# STM32F767VG.net
KiCad netlist of a schematic drawn in EAGLE
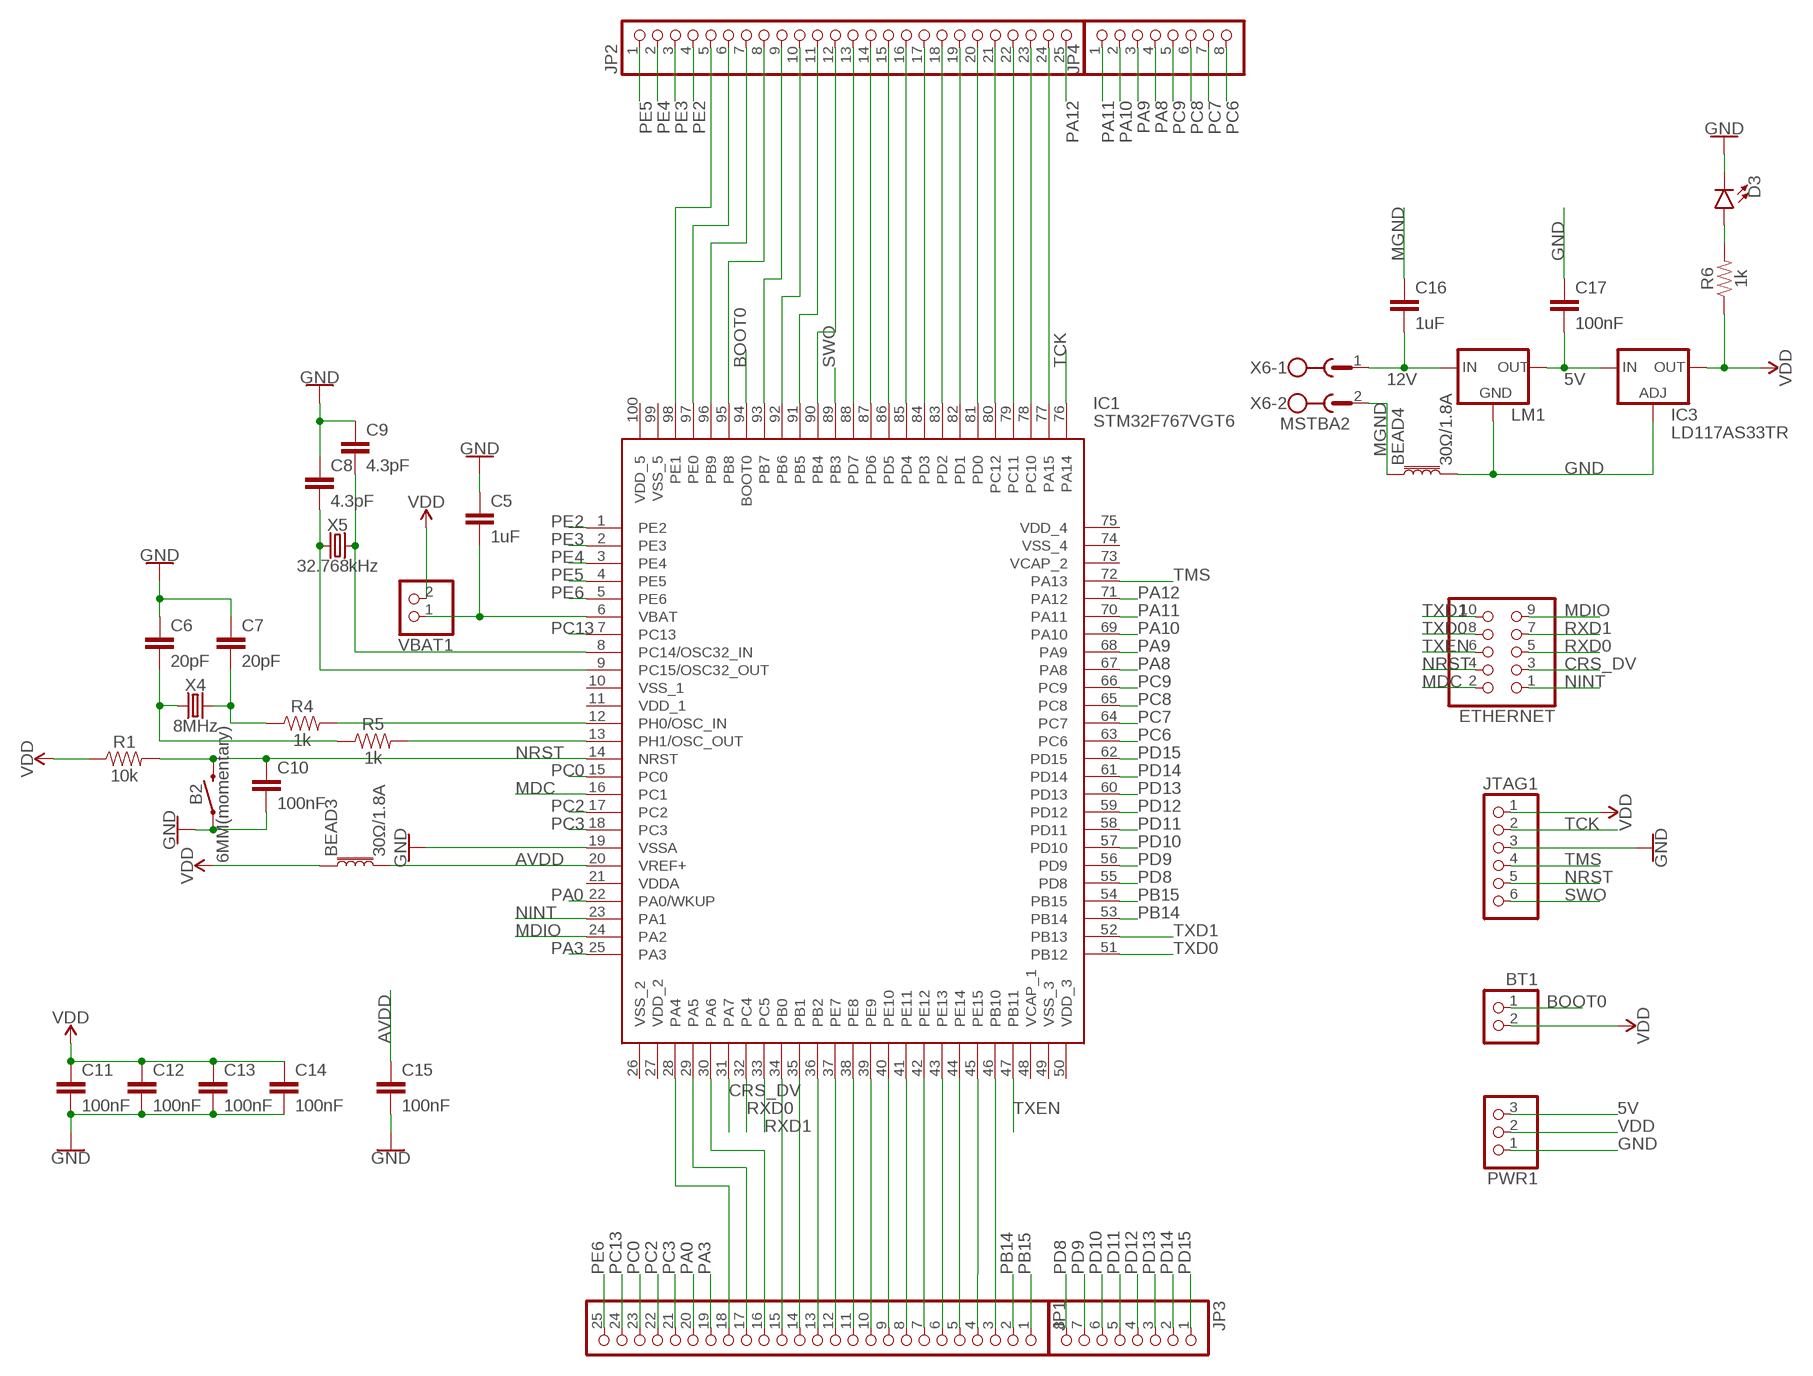
[diagram p0: schematic, sheet 1]

(export (version "E")
  (design (tool "Eeschema 10.0.6"))
  (components
    (comp (ref "B2")
      (value "6MM(momentary)")
      (footprint "eagle-import:TACTILE_SWITCH_PTH_6.0MM")
      (libsource (lib "eagle-import") (part "MOMENTARY-SWITCH-SPST-PTH-6.0MM"))
    )
    (comp (ref "BEAD3")
      (value "30Ω/1.8A")
      (footprint "eagle-import:0603")
      (libsource (lib "eagle-import") (part "FERRITE_BEAD-0603"))
    )
    (comp (ref "BEAD4")
      (value "30Ω/1.8A")
      (footprint "eagle-import:0603")
      (libsource (lib "eagle-import") (part "FERRITE_BEAD-0603"))
    )
    (comp (ref "BT1")
      (value "PINHD-1X2")
      (footprint "eagle-import:1X02")
      (libsource (lib "eagle-import") (part "PINHD-1X2"))
    )
    (comp (ref "C5")
      (value "1uF")
      (footprint "eagle-import:C050-030-075")
      (libsource (lib "eagle-import") (part "C5P"))
    )
    (comp (ref "C6")
      (value "20pF")
      (footprint "eagle-import:C025-030X050")
      (libsource (lib "eagle-import") (part "C2.5P"))
    )
    (comp (ref "C7")
      (value "20pF")
      (footprint "eagle-import:C025-030X050")
      (libsource (lib "eagle-import") (part "C2.5P"))
    )
    (comp (ref "C8")
      (value "4.3pF")
      (footprint "eagle-import:C025-030X050")
      (libsource (lib "eagle-import") (part "C2.5P"))
    )
    (comp (ref "C9")
      (value "4.3pF")
      (footprint "eagle-import:C025-030X050")
      (libsource (lib "eagle-import") (part "C2.5P"))
    )
    (comp (ref "C10")
      (value "100nF")
      (footprint "eagle-import:C025-030X050")
      (libsource (lib "eagle-import") (part "C2.5P"))
    )
    (comp (ref "C11")
      (value "100nF")
      (footprint "eagle-import:C025-030X050")
      (libsource (lib "eagle-import") (part "C2.5P"))
    )
    (comp (ref "C12")
      (value "100nF")
      (footprint "eagle-import:C025-030X050")
      (libsource (lib "eagle-import") (part "C2.5P"))
    )
    (comp (ref "C13")
      (value "100nF")
      (footprint "eagle-import:C025-030X050")
      (libsource (lib "eagle-import") (part "C2.5P"))
    )
    (comp (ref "C14")
      (value "100nF")
      (footprint "eagle-import:C025-030X050")
      (libsource (lib "eagle-import") (part "C2.5P"))
    )
    (comp (ref "C15")
      (value "100nF")
      (footprint "eagle-import:C025-030X050")
      (libsource (lib "eagle-import") (part "C2.5P"))
    )
    (comp (ref "C16")
      (value "1uF")
      (footprint "eagle-import:C050-030-075")
      (libsource (lib "eagle-import") (part "C5P"))
    )
    (comp (ref "C17")
      (value "100nF")
      (footprint "eagle-import:C025-030X050")
      (libsource (lib "eagle-import") (part "C2.5P"))
    )
    (comp (ref "D3")
      (value "LED5MM")
      (footprint "eagle-import:LED_5MM")
      (libsource (lib "eagle-import") (part "LED5MM"))
    )
    (comp (ref "ETHERNET")
      (value "PINHD-2X5")
      (footprint "eagle-import:2X05")
      (libsource (lib "eagle-import") (part "PINHD-2X5"))
    )
    (comp (ref "IC1")
      (value "STM32F767VGT6")
      (footprint "eagle-import:QFP50P1600X1600X160-100N")
      (libsource (lib "eagle-import") (part "STM32F767VGT6"))
    )
    (comp (ref "IC3")
      (value "LD117AS33TR")
      (footprint "eagle-import:SOT223")
      (libsource (lib "eagle-import") (part "LD117A?S33TR"))
    )
    (comp (ref "JP1")
      (value "PINHD-1X25")
      (footprint "eagle-import:1X25")
      (libsource (lib "eagle-import") (part "PINHD-1X25"))
    )
    (comp (ref "JP2")
      (value "PINHD-1X25")
      (footprint "eagle-import:1X25")
      (libsource (lib "eagle-import") (part "PINHD-1X25"))
    )
    (comp (ref "JP3")
      (value "PINHD-1X8")
      (footprint "eagle-import:1X08")
      (libsource (lib "eagle-import") (part "PINHD-1X8"))
    )
    (comp (ref "JP4")
      (value "PINHD-1X8")
      (footprint "eagle-import:1X08")
      (libsource (lib "eagle-import") (part "PINHD-1X8"))
    )
    (comp (ref "JTAG1")
      (value "PINHD-1X6")
      (footprint "eagle-import:1X06")
      (libsource (lib "eagle-import") (part "PINHD-1X6"))
    )
    (comp (ref "LM1")
      (value "V_REG_78XX-TO-220")
      (footprint "eagle-import:TO-220-ALT")
      (libsource (lib "eagle-import") (part "V_REG_78XX-TO-220"))
    )
    (comp (ref "PWR1")
      (value "PINHD-1X3")
      (footprint "eagle-import:1X03")
      (libsource (lib "eagle-import") (part "PINHD-1X3"))
    )
    (comp (ref "R1")
      (value "10k")
      (footprint "eagle-import:AXIAL-0.3")
      (libsource (lib "eagle-import") (part "10KOHM-HORIZ-1/4W-1%"))
    )
    (comp (ref "R4")
      (value "1k")
      (footprint "eagle-import:AXIAL-0.3")
      (libsource (lib "eagle-import") (part "10KOHM-HORIZ-1/4W-1%"))
    )
    (comp (ref "R5")
      (value "1k")
      (footprint "eagle-import:AXIAL-0.3")
      (libsource (lib "eagle-import") (part "10KOHM-HORIZ-1/4W-1%"))
    )
    (comp (ref "R6")
      (value "1k")
      (footprint "eagle-import:AXIAL-0.3")
      (libsource (lib "eagle-import") (part "1KOHM-HORIZ-1/4W-1%"))
    )
    (comp (ref "VBAT1")
      (value "PINHD-1X2")
      (footprint "eagle-import:1X02")
      (libsource (lib "eagle-import") (part "PINHD-1X2"))
    )
    (comp (ref "X4")
      (value "8MHz")
      (footprint "eagle-import:HC49UP")
      (libsource (lib "eagle-import") (part "CRYSTAL-8MHZSMD-HC49UP"))
    )
    (comp (ref "X5")
      (value "32.768kHz")
      (footprint "eagle-import:CRYSTAL-PTH-2X6-CYL")
      (libsource (lib "eagle-import") (part "CRYSTAL-32.768KHZPTH-2X6"))
    )
    (comp (ref "X6")
      (value "MSTBA2")
      (footprint "eagle-import:MSTBA2")
      (fields (field (name "MF") "FARNELL") (field (name "MPN") "1757242"))
      (libsource (lib "eagle-import") (part "MSTBA2"))
    )
  )
  (nets
    (net (code "1") (name "/5V") (class "Default")
      (node (ref "C17") (pin "2") (pinfunction "2_2") (pintype "passive"))
      (node (ref "IC3") (pin "3") (pinfunction "IN_3") (pintype "input"))
      (node (ref "LM1") (pin "OUT") (pinfunction "OUT_OUT") (pintype "passive"))
      (node (ref "PWR1") (pin "3") (pinfunction "3_3") (pintype "passive"))
    )
    (net (code "2") (name "/12V") (class "Default")
      (node (ref "C16") (pin "2") (pinfunction "2_2") (pintype "passive"))
      (node (ref "LM1") (pin "IN") (pinfunction "IN_IN") (pintype "input"))
      (node (ref "X6") (pin "1") (pinfunction "1_1") (pintype "passive"))
    )
    (net (code "3") (name "/AVDD") (class "Default")
      (node (ref "BEAD3") (pin "2") (pinfunction "2_2") (pintype "passive"))
      (node (ref "C15") (pin "1") (pinfunction "1_1") (pintype "passive"))
      (node (ref "IC1") (pin "20") (pinfunction "VREF+_20") (pintype "power_in"))
    )
    (net (code "4") (name "/BOOT0") (class "Default")
      (node (ref "BT1") (pin "1") (pinfunction "1_1") (pintype "passive"))
      (node (ref "IC1") (pin "94") (pinfunction "BOOT0_94") (pintype "bidirectional"))
    )
    (net (code "5") (name "/CRS_DV") (class "Default")
      (node (ref "ETHERNET") (pin "3") (pinfunction "3_3") (pintype "passive"))
      (node (ref "IC1") (pin "31") (pinfunction "PA7_31") (pintype "bidirectional"))
    )
    (net (code "6") (name "/MDC") (class "Default")
      (node (ref "ETHERNET") (pin "2") (pinfunction "2_2") (pintype "passive"))
      (node (ref "IC1") (pin "16") (pinfunction "PC1_16") (pintype "bidirectional"))
    )
    (net (code "7") (name "/MDIO") (class "Default")
      (node (ref "ETHERNET") (pin "9") (pinfunction "9_9") (pintype "passive"))
      (node (ref "IC1") (pin "24") (pinfunction "PA2_24") (pintype "bidirectional"))
    )
    (net (code "8") (name "/MGND") (class "Default")
      (node (ref "BEAD4") (pin "1") (pinfunction "1_1") (pintype "passive"))
      (node (ref "C16") (pin "1") (pinfunction "1_1") (pintype "passive"))
      (node (ref "X6") (pin "2") (pinfunction "1_2") (pintype "passive"))
    )
    (net (code "9") (name "/NINT") (class "Default")
      (node (ref "ETHERNET") (pin "1") (pinfunction "1_1") (pintype "passive"))
      (node (ref "IC1") (pin "23") (pinfunction "PA1_23") (pintype "bidirectional"))
    )
    (net (code "10") (name "/NRST") (class "Default")
      (node (ref "B2") (pin "3") (pinfunction "2_3") (pintype "passive"))
      (node (ref "C10") (pin "1") (pinfunction "1_1") (pintype "passive"))
      (node (ref "ETHERNET") (pin "4") (pinfunction "4_4") (pintype "passive"))
      (node (ref "IC1") (pin "14") (pinfunction "NRST_14") (pintype "bidirectional"))
      (node (ref "JTAG1") (pin "5") (pinfunction "5_5") (pintype "passive"))
      (node (ref "R1") (pin "P$2") (pinfunction "2_P$2") (pintype "passive"))
    )
    (net (code "11") (name "/PA0") (class "Default")
      (node (ref "IC1") (pin "22") (pinfunction "PA0/WKUP_22") (pintype "bidirectional"))
      (node (ref "JP1") (pin "20") (pinfunction "20_20") (pintype "passive"))
    )
    (net (code "12") (name "/PA3") (class "Default")
      (node (ref "IC1") (pin "25") (pinfunction "PA3_25") (pintype "bidirectional"))
      (node (ref "JP1") (pin "19") (pinfunction "19_19") (pintype "passive"))
    )
    (net (code "13") (name "/PA8") (class "Default")
      (node (ref "IC1") (pin "67") (pinfunction "PA8_67") (pintype "bidirectional"))
      (node (ref "JP4") (pin "4") (pinfunction "4_4") (pintype "passive"))
    )
    (net (code "14") (name "/PA9") (class "Default")
      (node (ref "IC1") (pin "68") (pinfunction "PA9_68") (pintype "bidirectional"))
      (node (ref "JP4") (pin "3") (pinfunction "3_3") (pintype "passive"))
    )
    (net (code "15") (name "/PA10") (class "Default")
      (node (ref "IC1") (pin "69") (pinfunction "PA10_69") (pintype "bidirectional"))
      (node (ref "JP4") (pin "2") (pinfunction "2_2") (pintype "passive"))
    )
    (net (code "16") (name "/PA11") (class "Default")
      (node (ref "IC1") (pin "70") (pinfunction "PA11_70") (pintype "bidirectional"))
      (node (ref "JP4") (pin "1") (pinfunction "1_1") (pintype "passive"))
    )
    (net (code "17") (name "/PA12") (class "Default")
      (node (ref "IC1") (pin "71") (pinfunction "PA12_71") (pintype "bidirectional"))
      (node (ref "JP2") (pin "25") (pinfunction "25_25") (pintype "passive"))
    )
    (net (code "18") (name "/PB14") (class "Default")
      (node (ref "IC1") (pin "53") (pinfunction "PB14_53") (pintype "bidirectional"))
      (node (ref "JP1") (pin "2") (pinfunction "2_2") (pintype "passive"))
    )
    (net (code "19") (name "/PB15") (class "Default")
      (node (ref "IC1") (pin "54") (pinfunction "PB15_54") (pintype "bidirectional"))
      (node (ref "JP1") (pin "1") (pinfunction "1_1") (pintype "passive"))
    )
    (net (code "20") (name "/PC0") (class "Default")
      (node (ref "IC1") (pin "15") (pinfunction "PC0_15") (pintype "bidirectional"))
      (node (ref "JP1") (pin "23") (pinfunction "23_23") (pintype "passive"))
    )
    (net (code "21") (name "/PC2") (class "Default")
      (node (ref "IC1") (pin "17") (pinfunction "PC2_17") (pintype "bidirectional"))
      (node (ref "JP1") (pin "22") (pinfunction "22_22") (pintype "passive"))
    )
    (net (code "22") (name "/PC3") (class "Default")
      (node (ref "IC1") (pin "18") (pinfunction "PC3_18") (pintype "bidirectional"))
      (node (ref "JP1") (pin "21") (pinfunction "21_21") (pintype "passive"))
    )
    (net (code "23") (name "/PC6") (class "Default")
      (node (ref "IC1") (pin "63") (pinfunction "PC6_63") (pintype "bidirectional"))
      (node (ref "JP4") (pin "8") (pinfunction "8_8") (pintype "passive"))
    )
    (net (code "24") (name "/PC7") (class "Default")
      (node (ref "IC1") (pin "64") (pinfunction "PC7_64") (pintype "bidirectional"))
      (node (ref "JP4") (pin "7") (pinfunction "7_7") (pintype "passive"))
    )
    (net (code "25") (name "/PC8") (class "Default")
      (node (ref "IC1") (pin "65") (pinfunction "PC8_65") (pintype "bidirectional"))
      (node (ref "JP4") (pin "6") (pinfunction "6_6") (pintype "passive"))
    )
    (net (code "26") (name "/PC9") (class "Default")
      (node (ref "IC1") (pin "66") (pinfunction "PC9_66") (pintype "bidirectional"))
      (node (ref "JP4") (pin "5") (pinfunction "5_5") (pintype "passive"))
    )
    (net (code "27") (name "/PC13") (class "Default")
      (node (ref "IC1") (pin "7") (pinfunction "PC13_7") (pintype "bidirectional"))
      (node (ref "JP1") (pin "24") (pinfunction "24_24") (pintype "passive"))
    )
    (net (code "28") (name "/PD8") (class "Default")
      (node (ref "IC1") (pin "55") (pinfunction "PD8_55") (pintype "bidirectional"))
      (node (ref "JP3") (pin "8") (pinfunction "8_8") (pintype "passive"))
    )
    (net (code "29") (name "/PD9") (class "Default")
      (node (ref "IC1") (pin "56") (pinfunction "PD9_56") (pintype "bidirectional"))
      (node (ref "JP3") (pin "7") (pinfunction "7_7") (pintype "passive"))
    )
    (net (code "30") (name "/PD10") (class "Default")
      (node (ref "IC1") (pin "57") (pinfunction "PD10_57") (pintype "bidirectional"))
      (node (ref "JP3") (pin "6") (pinfunction "6_6") (pintype "passive"))
    )
    (net (code "31") (name "/PD11") (class "Default")
      (node (ref "IC1") (pin "58") (pinfunction "PD11_58") (pintype "bidirectional"))
      (node (ref "JP3") (pin "5") (pinfunction "5_5") (pintype "passive"))
    )
    (net (code "32") (name "/PD12") (class "Default")
      (node (ref "IC1") (pin "59") (pinfunction "PD12_59") (pintype "bidirectional"))
      (node (ref "JP3") (pin "4") (pinfunction "4_4") (pintype "passive"))
    )
    (net (code "33") (name "/PD13") (class "Default")
      (node (ref "IC1") (pin "60") (pinfunction "PD13_60") (pintype "bidirectional"))
      (node (ref "JP3") (pin "3") (pinfunction "3_3") (pintype "passive"))
    )
    (net (code "34") (name "/PD14") (class "Default")
      (node (ref "IC1") (pin "61") (pinfunction "PD14_61") (pintype "bidirectional"))
      (node (ref "JP3") (pin "2") (pinfunction "2_2") (pintype "passive"))
    )
    (net (code "35") (name "/PD15") (class "Default")
      (node (ref "IC1") (pin "62") (pinfunction "PD15_62") (pintype "bidirectional"))
      (node (ref "JP3") (pin "1") (pinfunction "1_1") (pintype "passive"))
    )
    (net (code "36") (name "/PE2") (class "Default")
      (node (ref "IC1") (pin "1") (pinfunction "PE2_1") (pintype "bidirectional"))
      (node (ref "IC1") (pin "98") (pinfunction "PE1_98") (pintype "bidirectional"))
      (node (ref "JP2") (pin "4") (pinfunction "4_4") (pintype "passive"))
      (node (ref "JP2") (pin "5") (pinfunction "5_5") (pintype "passive"))
    )
    (net (code "37") (name "/PE3") (class "Default")
      (node (ref "IC1") (pin "2") (pinfunction "PE3_2") (pintype "bidirectional"))
      (node (ref "JP2") (pin "3") (pinfunction "3_3") (pintype "passive"))
    )
    (net (code "38") (name "/PE4") (class "Default")
      (node (ref "IC1") (pin "3") (pinfunction "PE4_3") (pintype "bidirectional"))
      (node (ref "JP2") (pin "2") (pinfunction "2_2") (pintype "passive"))
    )
    (net (code "39") (name "/PE5") (class "Default")
      (node (ref "IC1") (pin "4") (pinfunction "PE5_4") (pintype "bidirectional"))
      (node (ref "JP2") (pin "1") (pinfunction "1_1") (pintype "passive"))
    )
    (net (code "40") (name "/PE6") (class "Default")
      (node (ref "IC1") (pin "5") (pinfunction "PE6_5") (pintype "bidirectional"))
      (node (ref "JP1") (pin "25") (pinfunction "25_25") (pintype "passive"))
    )
    (net (code "41") (name "/RXD0") (class "Default")
      (node (ref "ETHERNET") (pin "5") (pinfunction "5_5") (pintype "passive"))
      (node (ref "IC1") (pin "32") (pinfunction "PC4_32") (pintype "bidirectional"))
    )
    (net (code "42") (name "/RXD1") (class "Default")
      (node (ref "ETHERNET") (pin "7") (pinfunction "7_7") (pintype "passive"))
      (node (ref "IC1") (pin "33") (pinfunction "PC5_33") (pintype "bidirectional"))
    )
    (net (code "43") (name "/SWO") (class "Default")
      (node (ref "IC1") (pin "89") (pinfunction "PB3_89") (pintype "bidirectional"))
      (node (ref "JTAG1") (pin "6") (pinfunction "6_6") (pintype "passive"))
    )
    (net (code "44") (name "/TCK") (class "Default")
      (node (ref "IC1") (pin "76") (pinfunction "PA14_76") (pintype "bidirectional"))
      (node (ref "JTAG1") (pin "2") (pinfunction "2_2") (pintype "passive"))
    )
    (net (code "45") (name "/TMS") (class "Default")
      (node (ref "IC1") (pin "72") (pinfunction "PA13_72") (pintype "bidirectional"))
      (node (ref "JTAG1") (pin "4") (pinfunction "4_4") (pintype "passive"))
    )
    (net (code "46") (name "/TXD0") (class "Default")
      (node (ref "ETHERNET") (pin "8") (pinfunction "8_8") (pintype "passive"))
      (node (ref "IC1") (pin "51") (pinfunction "PB12_51") (pintype "bidirectional"))
    )
    (net (code "47") (name "/TXD1") (class "Default")
      (node (ref "ETHERNET") (pin "10") (pinfunction "10_10") (pintype "passive"))
      (node (ref "IC1") (pin "52") (pinfunction "PB13_52") (pintype "bidirectional"))
    )
    (net (code "48") (name "/TXEN") (class "Default")
      (node (ref "ETHERNET") (pin "6") (pinfunction "6_6") (pintype "passive"))
      (node (ref "IC1") (pin "47") (pinfunction "PB11_47") (pintype "bidirectional"))
    )
    (net (code "49") (name "/VCAP_1") (class "Default")
      (node (ref "IC1") (pin "48") (pinfunction "VCAP_1_48") (pintype "power_in"))
    )
    (net (code "50") (name "/VCAP_2") (class "Default")
      (node (ref "IC1") (pin "73") (pinfunction "VCAP_2_73") (pintype "power_in"))
    )
    (net (code "51") (name "/VDDA") (class "Default")
      (node (ref "IC1") (pin "21") (pinfunction "VDDA_21") (pintype "power_in"))
    )
    (net (code "52") (name "/VDD_1") (class "Default")
      (node (ref "IC1") (pin "11") (pinfunction "VDD_1_11") (pintype "power_in"))
    )
    (net (code "53") (name "/VDD_2") (class "Default")
      (node (ref "IC1") (pin "27") (pinfunction "VDD_2_27") (pintype "power_in"))
    )
    (net (code "54") (name "/VDD_3") (class "Default")
      (node (ref "IC1") (pin "50") (pinfunction "VDD_3_50") (pintype "power_in"))
    )
    (net (code "55") (name "/VDD_4") (class "Default")
      (node (ref "IC1") (pin "75") (pinfunction "VDD_4_75") (pintype "power_in"))
    )
    (net (code "56") (name "/VDD_5") (class "Default")
      (node (ref "IC1") (pin "100") (pinfunction "VDD_5_100") (pintype "power_in"))
    )
    (net (code "57") (name "/VSS_1") (class "Default")
      (node (ref "IC1") (pin "10") (pinfunction "VSS_1_10") (pintype "power_in"))
    )
    (net (code "58") (name "/VSS_2") (class "Default")
      (node (ref "IC1") (pin "26") (pinfunction "VSS_2_26") (pintype "power_in"))
    )
    (net (code "59") (name "/VSS_3") (class "Default")
      (node (ref "IC1") (pin "49") (pinfunction "VSS_3_49") (pintype "power_in"))
    )
    (net (code "60") (name "/VSS_4") (class "Default")
      (node (ref "IC1") (pin "74") (pinfunction "VSS_4_74") (pintype "power_in"))
    )
    (net (code "61") (name "/VSS_5") (class "Default")
      (node (ref "IC1") (pin "99") (pinfunction "VSS_5_99") (pintype "power_in"))
    )
    (net (code "62") (name "GND") (class "Default")
      (node (ref "B2") (pin "1") (pinfunction "1_1") (pintype "passive"))
      (node (ref "BEAD4") (pin "2") (pinfunction "2_2") (pintype "passive"))
      (node (ref "C10") (pin "2") (pinfunction "2_2") (pintype "passive"))
      (node (ref "C11") (pin "2") (pinfunction "2_2") (pintype "passive"))
      (node (ref "C12") (pin "2") (pinfunction "2_2") (pintype "passive"))
      (node (ref "C13") (pin "2") (pinfunction "2_2") (pintype "passive"))
      (node (ref "C14") (pin "2") (pinfunction "2_2") (pintype "passive"))
      (node (ref "C15") (pin "2") (pinfunction "2_2") (pintype "passive"))
      (node (ref "C17") (pin "1") (pinfunction "1_1") (pintype "passive"))
      (node (ref "C5") (pin "1") (pinfunction "1_1") (pintype "passive"))
      (node (ref "C6") (pin "1") (pinfunction "1_1") (pintype "passive"))
      (node (ref "C7") (pin "1") (pinfunction "1_1") (pintype "passive"))
      (node (ref "C8") (pin "1") (pinfunction "1_1") (pintype "passive"))
      (node (ref "C9") (pin "1") (pinfunction "1_1") (pintype "passive"))
      (node (ref "D3") (pin "K") (pinfunction "C_K") (pintype "passive"))
      (node (ref "IC1") (pin "19") (pinfunction "VSSA_19") (pintype "power_in"))
      (node (ref "IC3") (pin "1") (pinfunction "ADJ_1") (pintype "input"))
      (node (ref "JTAG1") (pin "3") (pinfunction "3_3") (pintype "passive"))
      (node (ref "LM1") (pin "GND") (pinfunction "GND_GND") (pintype "input"))
      (node (ref "PWR1") (pin "1") (pinfunction "1_1") (pintype "passive"))
    )
    (net (code "63") (name "Net-(IC1-PA4)") (class "Default")
      (node (ref "IC1") (pin "28") (pinfunction "PA4_28") (pintype "bidirectional"))
      (node (ref "JP1") (pin "18") (pinfunction "18_18") (pintype "passive"))
    )
    (net (code "64") (name "Net-(IC1-PA5)") (class "Default")
      (node (ref "IC1") (pin "29") (pinfunction "PA5_29") (pintype "bidirectional"))
      (node (ref "JP1") (pin "17") (pinfunction "17_17") (pintype "passive"))
    )
    (net (code "65") (name "Net-(IC1-PA6)") (class "Default")
      (node (ref "IC1") (pin "30") (pinfunction "PA6_30") (pintype "bidirectional"))
      (node (ref "JP1") (pin "16") (pinfunction "16_16") (pintype "passive"))
    )
    (net (code "66") (name "Net-(IC1-PA15)") (class "Default")
      (node (ref "IC1") (pin "77") (pinfunction "PA15_77") (pintype "bidirectional"))
      (node (ref "JP2") (pin "24") (pinfunction "24_24") (pintype "passive"))
    )
    (net (code "67") (name "Net-(IC1-PB0)") (class "Default")
      (node (ref "IC1") (pin "34") (pinfunction "PB0_34") (pintype "bidirectional"))
      (node (ref "JP1") (pin "15") (pinfunction "15_15") (pintype "passive"))
    )
    (net (code "68") (name "Net-(IC1-PB1)") (class "Default")
      (node (ref "IC1") (pin "35") (pinfunction "PB1_35") (pintype "bidirectional"))
      (node (ref "JP1") (pin "14") (pinfunction "14_14") (pintype "passive"))
    )
    (net (code "69") (name "Net-(IC1-PB2)") (class "Default")
      (node (ref "IC1") (pin "36") (pinfunction "PB2_36") (pintype "bidirectional"))
      (node (ref "JP1") (pin "13") (pinfunction "13_13") (pintype "passive"))
    )
    (net (code "70") (name "Net-(IC1-PB4)") (class "Default")
      (node (ref "IC1") (pin "90") (pinfunction "PB4_90") (pintype "bidirectional"))
      (node (ref "JP2") (pin "12") (pinfunction "12_12") (pintype "passive"))
    )
    (net (code "71") (name "Net-(IC1-PB5)") (class "Default")
      (node (ref "IC1") (pin "91") (pinfunction "PB5_91") (pintype "bidirectional"))
      (node (ref "JP2") (pin "11") (pinfunction "11_11") (pintype "passive"))
    )
    (net (code "72") (name "Net-(IC1-PB6)") (class "Default")
      (node (ref "IC1") (pin "92") (pinfunction "PB6_92") (pintype "bidirectional"))
      (node (ref "JP2") (pin "10") (pinfunction "10_10") (pintype "passive"))
    )
    (net (code "73") (name "Net-(IC1-PB7)") (class "Default")
      (node (ref "IC1") (pin "93") (pinfunction "PB7_93") (pintype "bidirectional"))
      (node (ref "JP2") (pin "9") (pinfunction "9_9") (pintype "passive"))
    )
    (net (code "74") (name "Net-(IC1-PB8)") (class "Default")
      (node (ref "IC1") (pin "95") (pinfunction "PB8_95") (pintype "bidirectional"))
      (node (ref "JP2") (pin "8") (pinfunction "8_8") (pintype "passive"))
    )
    (net (code "75") (name "Net-(IC1-PB9)") (class "Default")
      (node (ref "IC1") (pin "96") (pinfunction "PB9_96") (pintype "bidirectional"))
      (node (ref "JP2") (pin "7") (pinfunction "7_7") (pintype "passive"))
    )
    (net (code "76") (name "Net-(IC1-PB10)") (class "Default")
      (node (ref "IC1") (pin "46") (pinfunction "PB10_46") (pintype "bidirectional"))
      (node (ref "JP1") (pin "3") (pinfunction "3_3") (pintype "passive"))
    )
    (net (code "77") (name "Net-(IC1-PC10)") (class "Default")
      (node (ref "IC1") (pin "78") (pinfunction "PC10_78") (pintype "bidirectional"))
      (node (ref "JP2") (pin "23") (pinfunction "23_23") (pintype "passive"))
    )
    (net (code "78") (name "Net-(IC1-PC11)") (class "Default")
      (node (ref "IC1") (pin "79") (pinfunction "PC11_79") (pintype "bidirectional"))
      (node (ref "JP2") (pin "22") (pinfunction "22_22") (pintype "passive"))
    )
    (net (code "79") (name "Net-(IC1-PC12)") (class "Default")
      (node (ref "IC1") (pin "80") (pinfunction "PC12_80") (pintype "bidirectional"))
      (node (ref "JP2") (pin "21") (pinfunction "21_21") (pintype "passive"))
    )
    (net (code "80") (name "Net-(IC1-PC14{slash}OSC32_IN)") (class "Default")
      (node (ref "C9") (pin "2") (pinfunction "2_2") (pintype "passive"))
      (node (ref "IC1") (pin "8") (pinfunction "PC14/OSC32_IN_8") (pintype "bidirectional"))
      (node (ref "X5") (pin "2") (pinfunction "2_2") (pintype "passive"))
    )
    (net (code "81") (name "Net-(IC1-PC15{slash}OSC32_OUT)") (class "Default")
      (node (ref "C8") (pin "2") (pinfunction "2_2") (pintype "passive"))
      (node (ref "IC1") (pin "9") (pinfunction "PC15/OSC32_OUT_9") (pintype "bidirectional"))
      (node (ref "X5") (pin "1") (pinfunction "1_1") (pintype "passive"))
    )
    (net (code "82") (name "Net-(IC1-PD0)") (class "Default")
      (node (ref "IC1") (pin "81") (pinfunction "PD0_81") (pintype "bidirectional"))
      (node (ref "JP2") (pin "20") (pinfunction "20_20") (pintype "passive"))
    )
    (net (code "83") (name "Net-(IC1-PD1)") (class "Default")
      (node (ref "IC1") (pin "82") (pinfunction "PD1_82") (pintype "bidirectional"))
      (node (ref "JP2") (pin "19") (pinfunction "19_19") (pintype "passive"))
    )
    (net (code "84") (name "Net-(IC1-PD2)") (class "Default")
      (node (ref "IC1") (pin "83") (pinfunction "PD2_83") (pintype "bidirectional"))
      (node (ref "JP2") (pin "18") (pinfunction "18_18") (pintype "passive"))
    )
    (net (code "85") (name "Net-(IC1-PD3)") (class "Default")
      (node (ref "IC1") (pin "84") (pinfunction "PD3_84") (pintype "bidirectional"))
      (node (ref "JP2") (pin "17") (pinfunction "17_17") (pintype "passive"))
    )
    (net (code "86") (name "Net-(IC1-PD4)") (class "Default")
      (node (ref "IC1") (pin "85") (pinfunction "PD4_85") (pintype "bidirectional"))
      (node (ref "JP2") (pin "16") (pinfunction "16_16") (pintype "passive"))
    )
    (net (code "87") (name "Net-(IC1-PD5)") (class "Default")
      (node (ref "IC1") (pin "86") (pinfunction "PD5_86") (pintype "bidirectional"))
      (node (ref "JP2") (pin "15") (pinfunction "15_15") (pintype "passive"))
    )
    (net (code "88") (name "Net-(IC1-PD6)") (class "Default")
      (node (ref "IC1") (pin "87") (pinfunction "PD6_87") (pintype "bidirectional"))
      (node (ref "JP2") (pin "14") (pinfunction "14_14") (pintype "passive"))
    )
    (net (code "89") (name "Net-(IC1-PD7)") (class "Default")
      (node (ref "IC1") (pin "88") (pinfunction "PD7_88") (pintype "bidirectional"))
      (node (ref "JP2") (pin "13") (pinfunction "13_13") (pintype "passive"))
    )
    (net (code "90") (name "Net-(IC1-PE0)") (class "Default")
      (node (ref "IC1") (pin "97") (pinfunction "PE0_97") (pintype "bidirectional"))
      (node (ref "JP2") (pin "6") (pinfunction "6_6") (pintype "passive"))
    )
    (net (code "91") (name "Net-(IC1-PE7)") (class "Default")
      (node (ref "IC1") (pin "37") (pinfunction "PE7_37") (pintype "bidirectional"))
      (node (ref "JP1") (pin "12") (pinfunction "12_12") (pintype "passive"))
    )
    (net (code "92") (name "Net-(IC1-PE8)") (class "Default")
      (node (ref "IC1") (pin "38") (pinfunction "PE8_38") (pintype "bidirectional"))
      (node (ref "JP1") (pin "11") (pinfunction "11_11") (pintype "passive"))
    )
    (net (code "93") (name "Net-(IC1-PE9)") (class "Default")
      (node (ref "IC1") (pin "39") (pinfunction "PE9_39") (pintype "bidirectional"))
      (node (ref "JP1") (pin "10") (pinfunction "10_10") (pintype "passive"))
    )
    (net (code "94") (name "Net-(IC1-PE10)") (class "Default")
      (node (ref "IC1") (pin "40") (pinfunction "PE10_40") (pintype "bidirectional"))
      (node (ref "JP1") (pin "9") (pinfunction "9_9") (pintype "passive"))
    )
    (net (code "95") (name "Net-(IC1-PE11)") (class "Default")
      (node (ref "IC1") (pin "41") (pinfunction "PE11_41") (pintype "bidirectional"))
      (node (ref "JP1") (pin "8") (pinfunction "8_8") (pintype "passive"))
    )
    (net (code "96") (name "Net-(IC1-PE12)") (class "Default")
      (node (ref "IC1") (pin "42") (pinfunction "PE12_42") (pintype "bidirectional"))
      (node (ref "JP1") (pin "7") (pinfunction "7_7") (pintype "passive"))
    )
    (net (code "97") (name "Net-(IC1-PE13)") (class "Default")
      (node (ref "IC1") (pin "43") (pinfunction "PE13_43") (pintype "bidirectional"))
      (node (ref "JP1") (pin "6") (pinfunction "6_6") (pintype "passive"))
    )
    (net (code "98") (name "Net-(IC1-PE14)") (class "Default")
      (node (ref "IC1") (pin "44") (pinfunction "PE14_44") (pintype "bidirectional"))
      (node (ref "JP1") (pin "5") (pinfunction "5_5") (pintype "passive"))
    )
    (net (code "99") (name "Net-(IC1-PE15)") (class "Default")
      (node (ref "IC1") (pin "45") (pinfunction "PE15_45") (pintype "bidirectional"))
      (node (ref "JP1") (pin "4") (pinfunction "4_4") (pintype "passive"))
    )
    (net (code "100") (name "Net-(IC1-PH0{slash}OSC_IN)") (class "Default")
      (node (ref "IC1") (pin "12") (pinfunction "PH0/OSC_IN_12") (pintype "bidirectional"))
      (node (ref "R4") (pin "P$2") (pinfunction "2_P$2") (pintype "passive"))
    )
    (net (code "101") (name "Net-(IC1-PH1{slash}OSC_OUT)") (class "Default")
      (node (ref "IC1") (pin "13") (pinfunction "PH1/OSC_OUT_13") (pintype "bidirectional"))
      (node (ref "R5") (pin "P$2") (pinfunction "2_P$2") (pintype "passive"))
    )
    (net (code "102") (name "Net-(IC1-VBAT)") (class "Default")
      (node (ref "C5") (pin "2") (pinfunction "2_2") (pintype "passive"))
      (node (ref "IC1") (pin "6") (pinfunction "VBAT_6") (pintype "power_in"))
      (node (ref "VBAT1") (pin "1") (pinfunction "1_1") (pintype "passive"))
    )
    (net (code "103") (name "Net-(R4-1)") (class "Default")
      (node (ref "C7") (pin "2") (pinfunction "2_2") (pintype "passive"))
      (node (ref "R4") (pin "P$1") (pinfunction "1_P$1") (pintype "passive"))
      (node (ref "X4") (pin "2") (pinfunction "2_2") (pintype "passive"))
    )
    (net (code "104") (name "Net-(R5-1)") (class "Default")
      (node (ref "C6") (pin "2") (pinfunction "2_2") (pintype "passive"))
      (node (ref "R5") (pin "P$1") (pinfunction "1_P$1") (pintype "passive"))
      (node (ref "X4") (pin "1") (pinfunction "1_1") (pintype "passive"))
    )
    (net (code "105") (name "Net-(R6-2)") (class "Default")
      (node (ref "D3") (pin "A") (pinfunction "A_A") (pintype "passive"))
      (node (ref "R6") (pin "P$2") (pinfunction "2_P$2") (pintype "passive"))
    )
    (net (code "106") (name "VDD") (class "Default")
      (node (ref "BEAD3") (pin "1") (pinfunction "1_1") (pintype "passive"))
      (node (ref "BT1") (pin "2") (pinfunction "2_2") (pintype "passive"))
      (node (ref "C11") (pin "1") (pinfunction "1_1") (pintype "passive"))
      (node (ref "C12") (pin "1") (pinfunction "1_1") (pintype "passive"))
      (node (ref "C13") (pin "1") (pinfunction "1_1") (pintype "passive"))
      (node (ref "C14") (pin "1") (pinfunction "1_1") (pintype "passive"))
      (node (ref "IC3") (pin "4") (pinfunction "OUT_4") (pintype "passive"))
      (node (ref "JTAG1") (pin "1") (pinfunction "1_1") (pintype "passive"))
      (node (ref "PWR1") (pin "2") (pinfunction "2_2") (pintype "passive"))
      (node (ref "R1") (pin "P$1") (pinfunction "1_P$1") (pintype "passive"))
      (node (ref "R6") (pin "P$1") (pinfunction "1_P$1") (pintype "passive"))
      (node (ref "VBAT1") (pin "2") (pinfunction "2_2") (pintype "passive"))
    )
  )
)
